# BLDC.net
KiCad netlist of a schematic drawn in EAGLE
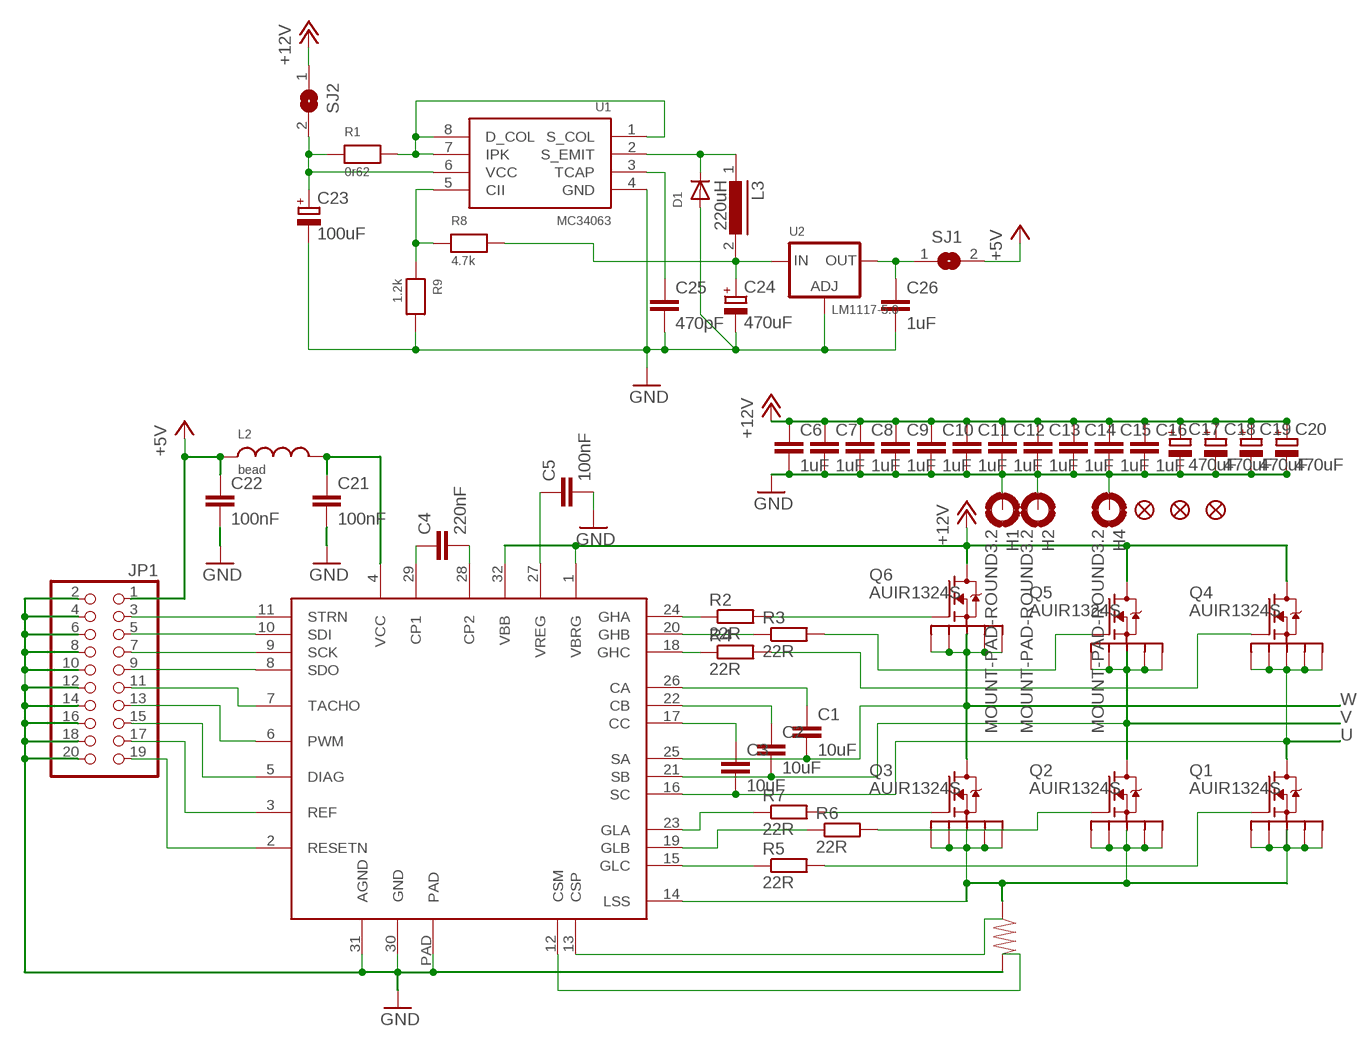
[diagram p0: schematic, sheet 1]

(export (version "E")
  (design (tool "Eeschema 10.0.6"))
  (components
    (comp (ref "C1")
      (value "10uF")
      (footprint "eagle-import:C0603K")
      (libsource (lib "eagle-import") (part "C-EUC0603K"))
    )
    (comp (ref "C2")
      (value "10uF")
      (footprint "eagle-import:C0603K")
      (libsource (lib "eagle-import") (part "C-EUC0603K"))
    )
    (comp (ref "C3")
      (value "10uF")
      (footprint "eagle-import:C0603K")
      (libsource (lib "eagle-import") (part "C-EUC0603K"))
    )
    (comp (ref "C4")
      (value "220nF")
      (footprint "eagle-import:C0603K")
      (libsource (lib "eagle-import") (part "C-EUC0603K"))
    )
    (comp (ref "C5")
      (value "100nF")
      (footprint "eagle-import:C0603K")
      (libsource (lib "eagle-import") (part "C-EUC0603K"))
    )
    (comp (ref "C6")
      (value "1uF")
      (footprint "eagle-import:C0603K")
      (libsource (lib "eagle-import") (part "C-EUC0603K"))
    )
    (comp (ref "C7")
      (value "1uF")
      (footprint "eagle-import:C0603K")
      (libsource (lib "eagle-import") (part "C-EUC0603K"))
    )
    (comp (ref "C8")
      (value "1uF")
      (footprint "eagle-import:C0603K")
      (libsource (lib "eagle-import") (part "C-EUC0603K"))
    )
    (comp (ref "C9")
      (value "1uF")
      (footprint "eagle-import:C0603K")
      (libsource (lib "eagle-import") (part "C-EUC0603K"))
    )
    (comp (ref "C10")
      (value "1uF")
      (footprint "eagle-import:C0603K")
      (libsource (lib "eagle-import") (part "C-EUC0603K"))
    )
    (comp (ref "C11")
      (value "1uF")
      (footprint "eagle-import:C0603K")
      (libsource (lib "eagle-import") (part "C-EUC0603K"))
    )
    (comp (ref "C12")
      (value "1uF")
      (footprint "eagle-import:C0603K")
      (libsource (lib "eagle-import") (part "C-EUC0603K"))
    )
    (comp (ref "C13")
      (value "1uF")
      (footprint "eagle-import:C0603K")
      (libsource (lib "eagle-import") (part "C-EUC0603K"))
    )
    (comp (ref "C14")
      (value "1uF")
      (footprint "eagle-import:C0603K")
      (libsource (lib "eagle-import") (part "C-EUC0603K"))
    )
    (comp (ref "C15")
      (value "1uF")
      (footprint "eagle-import:C0603K")
      (libsource (lib "eagle-import") (part "C-EUC0603K"))
    )
    (comp (ref "C16")
      (value "1uF")
      (footprint "eagle-import:C0603K")
      (libsource (lib "eagle-import") (part "C-EUC0603K"))
    )
    (comp (ref "C17")
      (value "470uF")
      (footprint "eagle-import:PANASONIC_D")
      (libsource (lib "eagle-import") (part "CPOL-EUD"))
    )
    (comp (ref "C18")
      (value "470uF")
      (footprint "eagle-import:PANASONIC_D")
      (libsource (lib "eagle-import") (part "CPOL-EUD"))
    )
    (comp (ref "C19")
      (value "470uF")
      (footprint "eagle-import:PANASONIC_D")
      (libsource (lib "eagle-import") (part "CPOL-EUD"))
    )
    (comp (ref "C20")
      (value "470uF")
      (footprint "eagle-import:PANASONIC_D")
      (libsource (lib "eagle-import") (part "CPOL-EUD"))
    )
    (comp (ref "C21")
      (value "100nF")
      (footprint "eagle-import:C0603K")
      (libsource (lib "eagle-import") (part "C-EUC0603K"))
    )
    (comp (ref "C22")
      (value "100nF")
      (footprint "eagle-import:C0603K")
      (libsource (lib "eagle-import") (part "C-EUC0603K"))
    )
    (comp (ref "C23")
      (value "100uF")
      (footprint "eagle-import:PANASONIC_D")
      (libsource (lib "eagle-import") (part "CPOL-EUD"))
    )
    (comp (ref "C24")
      (value "470uF")
      (footprint "eagle-import:PANASONIC_D")
      (libsource (lib "eagle-import") (part "CPOL-EUD"))
    )
    (comp (ref "C25")
      (value "470pF")
      (footprint "eagle-import:C0603K")
      (libsource (lib "eagle-import") (part "C-EUC0603K"))
    )
    (comp (ref "C26")
      (value "1uF")
      (footprint "eagle-import:C0603K")
      (libsource (lib "eagle-import") (part "C-EUC0603K"))
    )
    (comp (ref "D1")
      (value "DIODESOD-123")
      (footprint "eagle-import:SOD-123")
      (libsource (lib "eagle-import") (part "DIODESOD-123"))
    )
    (comp (ref "H1")
      (value "MOUNT-PAD-ROUND3.2")
      (footprint "eagle-import:3,2-PAD")
      (libsource (lib "eagle-import") (part "MOUNT-PAD-ROUND3.2"))
    )
    (comp (ref "H2")
      (value "MOUNT-PAD-ROUND3.2")
      (footprint "eagle-import:3,2-PAD")
      (libsource (lib "eagle-import") (part "MOUNT-PAD-ROUND3.2"))
    )
    (comp (ref "H4")
      (value "MOUNT-PAD-ROUND3.2")
      (footprint "eagle-import:3,2-PAD")
      (libsource (lib "eagle-import") (part "MOUNT-PAD-ROUND3.2"))
    )
    (comp (ref "IC1")
      (value "A4960")
      (footprint "eagle-import:LQFP32-7X7")
      (libsource (lib "eagle-import") (part "A4960"))
    )
    (comp (ref "JP1")
      (value "PINHD-2X10")
      (footprint "eagle-import:2X10")
      (libsource (lib "eagle-import") (part "PINHD-2X10"))
    )
    (comp (ref "JP2")
      (value "FIDUCIAL1X2")
      (footprint "eagle-import:FIDUCIAL-1X2")
      (libsource (lib "eagle-import") (part "FIDUCIAL1X2"))
    )
    (comp (ref "JP3")
      (value "FIDUCIAL1X2")
      (footprint "eagle-import:FIDUCIAL-1X2")
      (libsource (lib "eagle-import") (part "FIDUCIAL1X2"))
    )
    (comp (ref "JP4")
      (value "FIDUCIAL1X2")
      (footprint "eagle-import:FIDUCIAL-1X2")
      (libsource (lib "eagle-import") (part "FIDUCIAL1X2"))
    )
    (comp (ref "L2")
      (value "bead")
      (footprint "eagle-import:0603")
      (libsource (lib "eagle-import") (part "INDUCTOR0603"))
    )
    (comp (ref "L3")
      (value "220uH")
      (footprint "eagle-import:SLF7045")
      (libsource (lib "eagle-import") (part "SLF7045"))
    )
    (comp (ref "Q1")
      (value "AUIR1324S")
      (footprint "eagle-import:D2PAK-7")
      (libsource (lib "eagle-import") (part "NMOSFET-D2PAK-7"))
    )
    (comp (ref "Q2")
      (value "AUIR1324S")
      (footprint "eagle-import:D2PAK-7")
      (libsource (lib "eagle-import") (part "NMOSFET-D2PAK-7"))
    )
    (comp (ref "Q3")
      (value "AUIR1324S")
      (footprint "eagle-import:D2PAK-7")
      (libsource (lib "eagle-import") (part "NMOSFET-D2PAK-7"))
    )
    (comp (ref "Q4")
      (value "AUIR1324S")
      (footprint "eagle-import:D2PAK-7")
      (libsource (lib "eagle-import") (part "NMOSFET-D2PAK-7"))
    )
    (comp (ref "Q5")
      (value "AUIR1324S")
      (footprint "eagle-import:D2PAK-7")
      (libsource (lib "eagle-import") (part "NMOSFET-D2PAK-7"))
    )
    (comp (ref "Q6")
      (value "AUIR1324S")
      (footprint "eagle-import:D2PAK-7")
      (libsource (lib "eagle-import") (part "NMOSFET-D2PAK-7"))
    )
    (comp (ref "R1")
      (value "0r62")
      (footprint "eagle-import:0603")
      (libsource (lib "eagle-import") (part "RESISTOR0603"))
    )
    (comp (ref "R2")
      (value "22R")
      (footprint "eagle-import:R0603")
      (libsource (lib "eagle-import") (part "R-EU_R0603"))
    )
    (comp (ref "R3")
      (value "22R")
      (footprint "eagle-import:R0603")
      (libsource (lib "eagle-import") (part "R-EU_R0603"))
    )
    (comp (ref "R4")
      (value "22R")
      (footprint "eagle-import:R0603")
      (libsource (lib "eagle-import") (part "R-EU_R0603"))
    )
    (comp (ref "R5")
      (value "22R")
      (footprint "eagle-import:R0603")
      (libsource (lib "eagle-import") (part "R-EU_R0603"))
    )
    (comp (ref "R6")
      (value "22R")
      (footprint "eagle-import:R0603")
      (libsource (lib "eagle-import") (part "R-EU_R0603"))
    )
    (comp (ref "R7")
      (value "22R")
      (footprint "eagle-import:R0603")
      (libsource (lib "eagle-import") (part "R-EU_R0603"))
    )
    (comp (ref "R8")
      (value "4.7k")
      (footprint "eagle-import:0603")
      (libsource (lib "eagle-import") (part "RESISTOR0603"))
    )
    (comp (ref "R9")
      (value "1.2k")
      (footprint "eagle-import:0603")
      (libsource (lib "eagle-import") (part "RESISTOR0603"))
    )
    (comp (ref "SJ1")
      (value "SOLDERJUMPERREFLOW")
      (footprint "eagle-import:SOLDERJUMPER_REFLOW")
      (libsource (lib "eagle-import") (part "SOLDERJUMPERREFLOW"))
    )
    (comp (ref "SJ2")
      (value "SOLDERJUMPERREFLOW")
      (footprint "eagle-import:SOLDERJUMPER_REFLOW")
      (libsource (lib "eagle-import") (part "SOLDERJUMPERREFLOW"))
    )
    (comp (ref "U1")
      (value "MC34063")
      (footprint "eagle-import:SOIC8")
      (libsource (lib "eagle-import") (part "MC34063A"))
    )
    (comp (ref "U2")
      (value "LM1117-5.0")
      (footprint "eagle-import:SOT223-R")
      (libsource (lib "eagle-import") (part "LM1117SOT223-REFLOW"))
    )
  )
  (nets
    (net (code "1") (name "+5V") (class "Default")
      (node (ref "C22") (pin "1") (pinfunction "1_1") (pintype "passive"))
      (node (ref "JP1") (pin "1") (pinfunction "1_1") (pintype "passive"))
      (node (ref "L2") (pin "1") (pinfunction "1_1") (pintype "passive"))
      (node (ref "SJ1") (pin "2") (pinfunction "2_2") (pintype "passive"))
    )
    (net (code "2") (name "+12V") (class "Default")
      (node (ref "C10") (pin "1") (pinfunction "1_1") (pintype "passive"))
      (node (ref "C11") (pin "1") (pinfunction "1_1") (pintype "passive"))
      (node (ref "C12") (pin "1") (pinfunction "1_1") (pintype "passive"))
      (node (ref "C13") (pin "1") (pinfunction "1_1") (pintype "passive"))
      (node (ref "C14") (pin "1") (pinfunction "1_1") (pintype "passive"))
      (node (ref "C15") (pin "1") (pinfunction "1_1") (pintype "passive"))
      (node (ref "C16") (pin "1") (pinfunction "1_1") (pintype "passive"))
      (node (ref "C17") (pin "+") (pinfunction "+_+") (pintype "passive"))
      (node (ref "C18") (pin "+") (pinfunction "+_+") (pintype "passive"))
      (node (ref "C19") (pin "+") (pinfunction "+_+") (pintype "passive"))
      (node (ref "C20") (pin "+") (pinfunction "+_+") (pintype "passive"))
      (node (ref "C6") (pin "1") (pinfunction "1_1") (pintype "passive"))
      (node (ref "C7") (pin "1") (pinfunction "1_1") (pintype "passive"))
      (node (ref "C8") (pin "1") (pinfunction "1_1") (pintype "passive"))
      (node (ref "C9") (pin "1") (pinfunction "1_1") (pintype "passive"))
      (node (ref "IC1") (pin "1") (pinfunction "VBRG_1") (pintype "power_in"))
      (node (ref "IC1") (pin "32") (pinfunction "VBB_32") (pintype "power_in"))
      (node (ref "Q4") (pin "D") (pinfunction "D_D") (pintype "passive"))
      (node (ref "Q5") (pin "D") (pinfunction "D_D") (pintype "passive"))
      (node (ref "Q6") (pin "D") (pinfunction "D_D") (pintype "passive"))
      (node (ref "SJ2") (pin "1") (pinfunction "1_1") (pintype "passive"))
    )
    (net (code "3") (name "/U") (class "Default")
      (node (ref "C3") (pin "2") (pinfunction "2_2") (pintype "passive"))
      (node (ref "IC1") (pin "16") (pinfunction "SC_16") (pintype "bidirectional"))
      (node (ref "Q1") (pin "D") (pinfunction "D_D") (pintype "passive"))
      (node (ref "Q4") (pin "S1") (pinfunction "S1_S1") (pintype "passive"))
      (node (ref "Q4") (pin "S2") (pinfunction "S2_S2") (pintype "passive"))
      (node (ref "Q4") (pin "S3") (pinfunction "S3_S3") (pintype "passive"))
      (node (ref "Q4") (pin "S4") (pinfunction "S4_S4") (pintype "passive"))
      (node (ref "Q4") (pin "S5") (pinfunction "S5_S5") (pintype "passive"))
    )
    (net (code "4") (name "/V") (class "Default")
      (node (ref "C2") (pin "2") (pinfunction "2_2") (pintype "passive"))
      (node (ref "IC1") (pin "21") (pinfunction "SB_21") (pintype "bidirectional"))
      (node (ref "Q2") (pin "D") (pinfunction "D_D") (pintype "passive"))
      (node (ref "Q5") (pin "S1") (pinfunction "S1_S1") (pintype "passive"))
      (node (ref "Q5") (pin "S2") (pinfunction "S2_S2") (pintype "passive"))
      (node (ref "Q5") (pin "S3") (pinfunction "S3_S3") (pintype "passive"))
      (node (ref "Q5") (pin "S4") (pinfunction "S4_S4") (pintype "passive"))
      (node (ref "Q5") (pin "S5") (pinfunction "S5_S5") (pintype "passive"))
    )
    (net (code "5") (name "/W") (class "Default")
      (node (ref "C1") (pin "2") (pinfunction "2_2") (pintype "passive"))
      (node (ref "IC1") (pin "25") (pinfunction "SA_25") (pintype "bidirectional"))
      (node (ref "Q3") (pin "D") (pinfunction "D_D") (pintype "passive"))
      (node (ref "Q6") (pin "S1") (pinfunction "S1_S1") (pintype "passive"))
      (node (ref "Q6") (pin "S2") (pinfunction "S2_S2") (pintype "passive"))
      (node (ref "Q6") (pin "S3") (pinfunction "S3_S3") (pintype "passive"))
      (node (ref "Q6") (pin "S4") (pinfunction "S4_S4") (pintype "passive"))
      (node (ref "Q6") (pin "S5") (pinfunction "S5_S5") (pintype "passive"))
    )
    (net (code "6") (name "GND") (class "Default")
      (node (ref "C10") (pin "2") (pinfunction "2_2") (pintype "passive"))
      (node (ref "C11") (pin "2") (pinfunction "2_2") (pintype "passive"))
      (node (ref "C12") (pin "2") (pinfunction "2_2") (pintype "passive"))
      (node (ref "C13") (pin "2") (pinfunction "2_2") (pintype "passive"))
      (node (ref "C14") (pin "2") (pinfunction "2_2") (pintype "passive"))
      (node (ref "C15") (pin "2") (pinfunction "2_2") (pintype "passive"))
      (node (ref "C16") (pin "2") (pinfunction "2_2") (pintype "passive"))
      (node (ref "C17") (pin "-") (pinfunction "-_-") (pintype "passive"))
      (node (ref "C18") (pin "-") (pinfunction "-_-") (pintype "passive"))
      (node (ref "C19") (pin "-") (pinfunction "-_-") (pintype "passive"))
      (node (ref "C20") (pin "-") (pinfunction "-_-") (pintype "passive"))
      (node (ref "C21") (pin "2") (pinfunction "2_2") (pintype "passive"))
      (node (ref "C22") (pin "2") (pinfunction "2_2") (pintype "passive"))
      (node (ref "C23") (pin "-") (pinfunction "-_-") (pintype "passive"))
      (node (ref "C24") (pin "-") (pinfunction "-_-") (pintype "passive"))
      (node (ref "C25") (pin "2") (pinfunction "2_2") (pintype "passive"))
      (node (ref "C26") (pin "2") (pinfunction "2_2") (pintype "passive"))
      (node (ref "C5") (pin "2") (pinfunction "2_2") (pintype "passive"))
      (node (ref "C6") (pin "2") (pinfunction "2_2") (pintype "passive"))
      (node (ref "C7") (pin "2") (pinfunction "2_2") (pintype "passive"))
      (node (ref "C8") (pin "2") (pinfunction "2_2") (pintype "passive"))
      (node (ref "C9") (pin "2") (pinfunction "2_2") (pintype "passive"))
      (node (ref "D1") (pin "A") (pinfunction "A_A") (pintype "passive"))
      (node (ref "H1") (pin "B3,2") (pinfunction "MOUNT_B3,2") (pintype "passive"))
      (node (ref "H2") (pin "B3,2") (pinfunction "MOUNT_B3,2") (pintype "passive"))
      (node (ref "H4") (pin "B3,2") (pinfunction "MOUNT_B3,2") (pintype "passive"))
      (node (ref "IC1") (pin "30") (pinfunction "GND_30") (pintype "power_in"))
      (node (ref "IC1") (pin "31") (pinfunction "AGND_31") (pintype "power_in"))
      (node (ref "IC1") (pin "PAD") (pinfunction "PAD_PAD") (pintype "power_in"))
      (node (ref "JP1") (pin "10") (pinfunction "10_10") (pintype "passive"))
      (node (ref "JP1") (pin "12") (pinfunction "12_12") (pintype "passive"))
      (node (ref "JP1") (pin "14") (pinfunction "14_14") (pintype "passive"))
      (node (ref "JP1") (pin "16") (pinfunction "16_16") (pintype "passive"))
      (node (ref "JP1") (pin "18") (pinfunction "18_18") (pintype "passive"))
      (node (ref "JP1") (pin "2") (pinfunction "2_2") (pintype "passive"))
      (node (ref "JP1") (pin "20") (pinfunction "20_20") (pintype "passive"))
      (node (ref "JP1") (pin "4") (pinfunction "4_4") (pintype "passive"))
      (node (ref "JP1") (pin "6") (pinfunction "6_6") (pintype "passive"))
      (node (ref "JP1") (pin "8") (pinfunction "8_8") (pintype "passive"))
      (node (ref "R9") (pin "2") (pinfunction "2_2") (pintype "passive"))
      (node (ref "U1") (pin "4") (pinfunction "GND_4") (pintype "bidirectional"))
      (node (ref "U2") (pin "1") (pinfunction "ADJ_1") (pintype "input"))
    )
    (net (code "7") (name "Net-(IC1-CA)") (class "Default")
      (node (ref "C1") (pin "1") (pinfunction "1_1") (pintype "passive"))
      (node (ref "IC1") (pin "26") (pinfunction "CA_26") (pintype "bidirectional"))
    )
    (net (code "8") (name "Net-(IC1-CB)") (class "Default")
      (node (ref "C2") (pin "1") (pinfunction "1_1") (pintype "passive"))
      (node (ref "IC1") (pin "22") (pinfunction "CB_22") (pintype "bidirectional"))
    )
    (net (code "9") (name "Net-(IC1-CC)") (class "Default")
      (node (ref "C3") (pin "1") (pinfunction "1_1") (pintype "passive"))
      (node (ref "IC1") (pin "17") (pinfunction "CC_17") (pintype "bidirectional"))
    )
    (net (code "10") (name "Net-(IC1-CP1)") (class "Default")
      (node (ref "C4") (pin "1") (pinfunction "1_1") (pintype "passive"))
      (node (ref "IC1") (pin "29") (pinfunction "CP1_29") (pintype "bidirectional"))
    )
    (net (code "11") (name "Net-(IC1-CP2)") (class "Default")
      (node (ref "C4") (pin "2") (pinfunction "2_2") (pintype "passive"))
      (node (ref "IC1") (pin "28") (pinfunction "CP2_28") (pintype "bidirectional"))
    )
    (net (code "12") (name "Net-(IC1-DIAG)") (class "Default")
      (node (ref "IC1") (pin "5") (pinfunction "DIAG_5") (pintype "bidirectional"))
      (node (ref "JP1") (pin "15") (pinfunction "15_15") (pintype "passive"))
    )
    (net (code "13") (name "Net-(IC1-GHA)") (class "Default")
      (node (ref "IC1") (pin "24") (pinfunction "GHA_24") (pintype "bidirectional"))
      (node (ref "R2") (pin "1") (pinfunction "1_1") (pintype "passive"))
    )
    (net (code "14") (name "Net-(IC1-GHB)") (class "Default")
      (node (ref "IC1") (pin "20") (pinfunction "GHB_20") (pintype "bidirectional"))
      (node (ref "R3") (pin "1") (pinfunction "1_1") (pintype "passive"))
    )
    (net (code "15") (name "Net-(IC1-GHC)") (class "Default")
      (node (ref "IC1") (pin "18") (pinfunction "GHC_18") (pintype "bidirectional"))
      (node (ref "R4") (pin "1") (pinfunction "1_1") (pintype "passive"))
    )
    (net (code "16") (name "Net-(IC1-GLA)") (class "Default")
      (node (ref "IC1") (pin "23") (pinfunction "GLA_23") (pintype "bidirectional"))
      (node (ref "R7") (pin "1") (pinfunction "1_1") (pintype "passive"))
    )
    (net (code "17") (name "Net-(IC1-GLB)") (class "Default")
      (node (ref "IC1") (pin "19") (pinfunction "GLB_19") (pintype "bidirectional"))
      (node (ref "R6") (pin "1") (pinfunction "1_1") (pintype "passive"))
    )
    (net (code "18") (name "Net-(IC1-GLC)") (class "Default")
      (node (ref "IC1") (pin "15") (pinfunction "GLC_15") (pintype "bidirectional"))
      (node (ref "R5") (pin "1") (pinfunction "1_1") (pintype "passive"))
    )
    (net (code "19") (name "Net-(IC1-LSS)") (class "Default")
      (node (ref "IC1") (pin "14") (pinfunction "LSS_14") (pintype "input"))
      (node (ref "Q1") (pin "S1") (pinfunction "S1_S1") (pintype "passive"))
      (node (ref "Q1") (pin "S2") (pinfunction "S2_S2") (pintype "passive"))
      (node (ref "Q1") (pin "S3") (pinfunction "S3_S3") (pintype "passive"))
      (node (ref "Q1") (pin "S4") (pinfunction "S4_S4") (pintype "passive"))
      (node (ref "Q1") (pin "S5") (pinfunction "S5_S5") (pintype "passive"))
      (node (ref "Q2") (pin "S1") (pinfunction "S1_S1") (pintype "passive"))
      (node (ref "Q2") (pin "S2") (pinfunction "S2_S2") (pintype "passive"))
      (node (ref "Q2") (pin "S3") (pinfunction "S3_S3") (pintype "passive"))
      (node (ref "Q2") (pin "S4") (pinfunction "S4_S4") (pintype "passive"))
      (node (ref "Q2") (pin "S5") (pinfunction "S5_S5") (pintype "passive"))
      (node (ref "Q3") (pin "S1") (pinfunction "S1_S1") (pintype "passive"))
      (node (ref "Q3") (pin "S2") (pinfunction "S2_S2") (pintype "passive"))
      (node (ref "Q3") (pin "S3") (pinfunction "S3_S3") (pintype "passive"))
      (node (ref "Q3") (pin "S4") (pinfunction "S4_S4") (pintype "passive"))
      (node (ref "Q3") (pin "S5") (pinfunction "S5_S5") (pintype "passive"))
    )
    (net (code "20") (name "Net-(IC1-PWM)") (class "Default")
      (node (ref "IC1") (pin "6") (pinfunction "PWM_6") (pintype "output"))
      (node (ref "JP1") (pin "13") (pinfunction "13_13") (pintype "passive"))
    )
    (net (code "21") (name "Net-(IC1-REF)") (class "Default")
      (node (ref "IC1") (pin "3") (pinfunction "REF_3") (pintype "input"))
      (node (ref "JP1") (pin "17") (pinfunction "17_17") (pintype "passive"))
    )
    (net (code "22") (name "Net-(IC1-RESETN)") (class "Default")
      (node (ref "IC1") (pin "2") (pinfunction "RESETN_2") (pintype "bidirectional"))
      (node (ref "JP1") (pin "19") (pinfunction "19_19") (pintype "passive"))
    )
    (net (code "23") (name "Net-(IC1-SCK)") (class "Default")
      (node (ref "IC1") (pin "9") (pinfunction "SCK_9") (pintype "input"))
      (node (ref "JP1") (pin "7") (pinfunction "7_7") (pintype "passive"))
    )
    (net (code "24") (name "Net-(IC1-SDI)") (class "Default")
      (node (ref "IC1") (pin "10") (pinfunction "SDI_10") (pintype "input"))
      (node (ref "JP1") (pin "5") (pinfunction "5_5") (pintype "passive"))
    )
    (net (code "25") (name "Net-(IC1-SDO)") (class "Default")
      (node (ref "IC1") (pin "8") (pinfunction "SDO_8") (pintype "output"))
      (node (ref "JP1") (pin "9") (pinfunction "9_9") (pintype "passive"))
    )
    (net (code "26") (name "Net-(IC1-STRN)") (class "Default")
      (node (ref "IC1") (pin "11") (pinfunction "STRN_11") (pintype "input"))
      (node (ref "JP1") (pin "3") (pinfunction "3_3") (pintype "passive"))
    )
    (net (code "27") (name "Net-(IC1-TACHO)") (class "Default")
      (node (ref "IC1") (pin "7") (pinfunction "TACHO_7") (pintype "bidirectional"))
      (node (ref "JP1") (pin "11") (pinfunction "11_11") (pintype "passive"))
    )
    (net (code "28") (name "Net-(IC1-VCC)") (class "Default")
      (node (ref "C21") (pin "1") (pinfunction "1_1") (pintype "passive"))
      (node (ref "IC1") (pin "4") (pinfunction "VCC_4") (pintype "power_in"))
      (node (ref "L2") (pin "2") (pinfunction "2_2") (pintype "passive"))
    )
    (net (code "29") (name "Net-(IC1-VREG)") (class "Default")
      (node (ref "C5") (pin "1") (pinfunction "1_1") (pintype "passive"))
      (node (ref "IC1") (pin "27") (pinfunction "VREG_27") (pintype "power_in"))
    )
    (net (code "30") (name "Net-(Q1-PadG)") (class "Default")
      (node (ref "Q1") (pin "G") (pinfunction "G_G") (pintype "passive"))
      (node (ref "R5") (pin "2") (pinfunction "2_2") (pintype "passive"))
    )
    (net (code "31") (name "Net-(Q2-PadG)") (class "Default")
      (node (ref "Q2") (pin "G") (pinfunction "G_G") (pintype "passive"))
      (node (ref "R6") (pin "2") (pinfunction "2_2") (pintype "passive"))
    )
    (net (code "32") (name "Net-(Q3-PadG)") (class "Default")
      (node (ref "Q3") (pin "G") (pinfunction "G_G") (pintype "passive"))
      (node (ref "R7") (pin "2") (pinfunction "2_2") (pintype "passive"))
    )
    (net (code "33") (name "Net-(Q4-PadG)") (class "Default")
      (node (ref "Q4") (pin "G") (pinfunction "G_G") (pintype "passive"))
      (node (ref "R4") (pin "2") (pinfunction "2_2") (pintype "passive"))
    )
    (net (code "34") (name "Net-(Q5-PadG)") (class "Default")
      (node (ref "Q5") (pin "G") (pinfunction "G_G") (pintype "passive"))
      (node (ref "R3") (pin "2") (pinfunction "2_2") (pintype "passive"))
    )
    (net (code "35") (name "Net-(Q6-PadG)") (class "Default")
      (node (ref "Q6") (pin "G") (pinfunction "G_G") (pintype "passive"))
      (node (ref "R2") (pin "2") (pinfunction "2_2") (pintype "passive"))
    )
    (net (code "36") (name "Net-(U1-CII)") (class "Default")
      (node (ref "R8") (pin "1") (pinfunction "1_1") (pintype "passive"))
      (node (ref "R9") (pin "1") (pinfunction "1_1") (pintype "passive"))
      (node (ref "U1") (pin "5") (pinfunction "CII_5") (pintype "bidirectional"))
    )
    (net (code "37") (name "Net-(U1-D_COL)") (class "Default")
      (node (ref "R1") (pin "2") (pinfunction "2_2") (pintype "passive"))
      (node (ref "U1") (pin "1") (pinfunction "S_COL_1") (pintype "bidirectional"))
      (node (ref "U1") (pin "7") (pinfunction "IPK_7") (pintype "bidirectional"))
      (node (ref "U1") (pin "8") (pinfunction "D_COL_8") (pintype "bidirectional"))
    )
    (net (code "38") (name "Net-(U1-S_EMIT)") (class "Default")
      (node (ref "D1") (pin "C") (pinfunction "C_C") (pintype "passive"))
      (node (ref "L3") (pin "1") (pinfunction "1_1") (pintype "passive"))
      (node (ref "U1") (pin "2") (pinfunction "S_EMIT_2") (pintype "bidirectional"))
    )
    (net (code "39") (name "Net-(U1-TCAP)") (class "Default")
      (node (ref "C25") (pin "1") (pinfunction "1_1") (pintype "passive"))
      (node (ref "U1") (pin "3") (pinfunction "TCAP_3") (pintype "bidirectional"))
    )
    (net (code "40") (name "Net-(U1-VCC)") (class "Default")
      (node (ref "C23") (pin "+") (pinfunction "+_+") (pintype "passive"))
      (node (ref "R1") (pin "1") (pinfunction "1_1") (pintype "passive"))
      (node (ref "SJ2") (pin "2") (pinfunction "2_2") (pintype "passive"))
      (node (ref "U1") (pin "6") (pinfunction "VCC_6") (pintype "bidirectional"))
    )
    (net (code "41") (name "Net-(U2-IN)") (class "Default")
      (node (ref "C24") (pin "+") (pinfunction "+_+") (pintype "passive"))
      (node (ref "L3") (pin "2") (pinfunction "2_2") (pintype "passive"))
      (node (ref "R8") (pin "2") (pinfunction "2_2") (pintype "passive"))
      (node (ref "U2") (pin "3") (pinfunction "IN_3") (pintype "input"))
    )
    (net (code "42") (name "Net-(U2-OUT)") (class "Default")
      (node (ref "C26") (pin "1") (pinfunction "1_1") (pintype "passive"))
      (node (ref "SJ1") (pin "1") (pinfunction "1_1") (pintype "passive"))
      (node (ref "U2") (pin "2") (pinfunction "OUT_2") (pintype "passive"))
    )
    (net (code "43") (name "unconnected-(IC1-CSM-Pad12)") (class "Default")
      (node (ref "IC1") (pin "12") (pinfunction "CSM_12") (pintype "input"))
    )
    (net (code "44") (name "unconnected-(IC1-CSP-Pad13)") (class "Default")
      (node (ref "IC1") (pin "13") (pinfunction "CSP_13") (pintype "input"))
    )
  )
)
